# ESP32Breakout.net
KiCad netlist of a schematic drawn in EAGLE
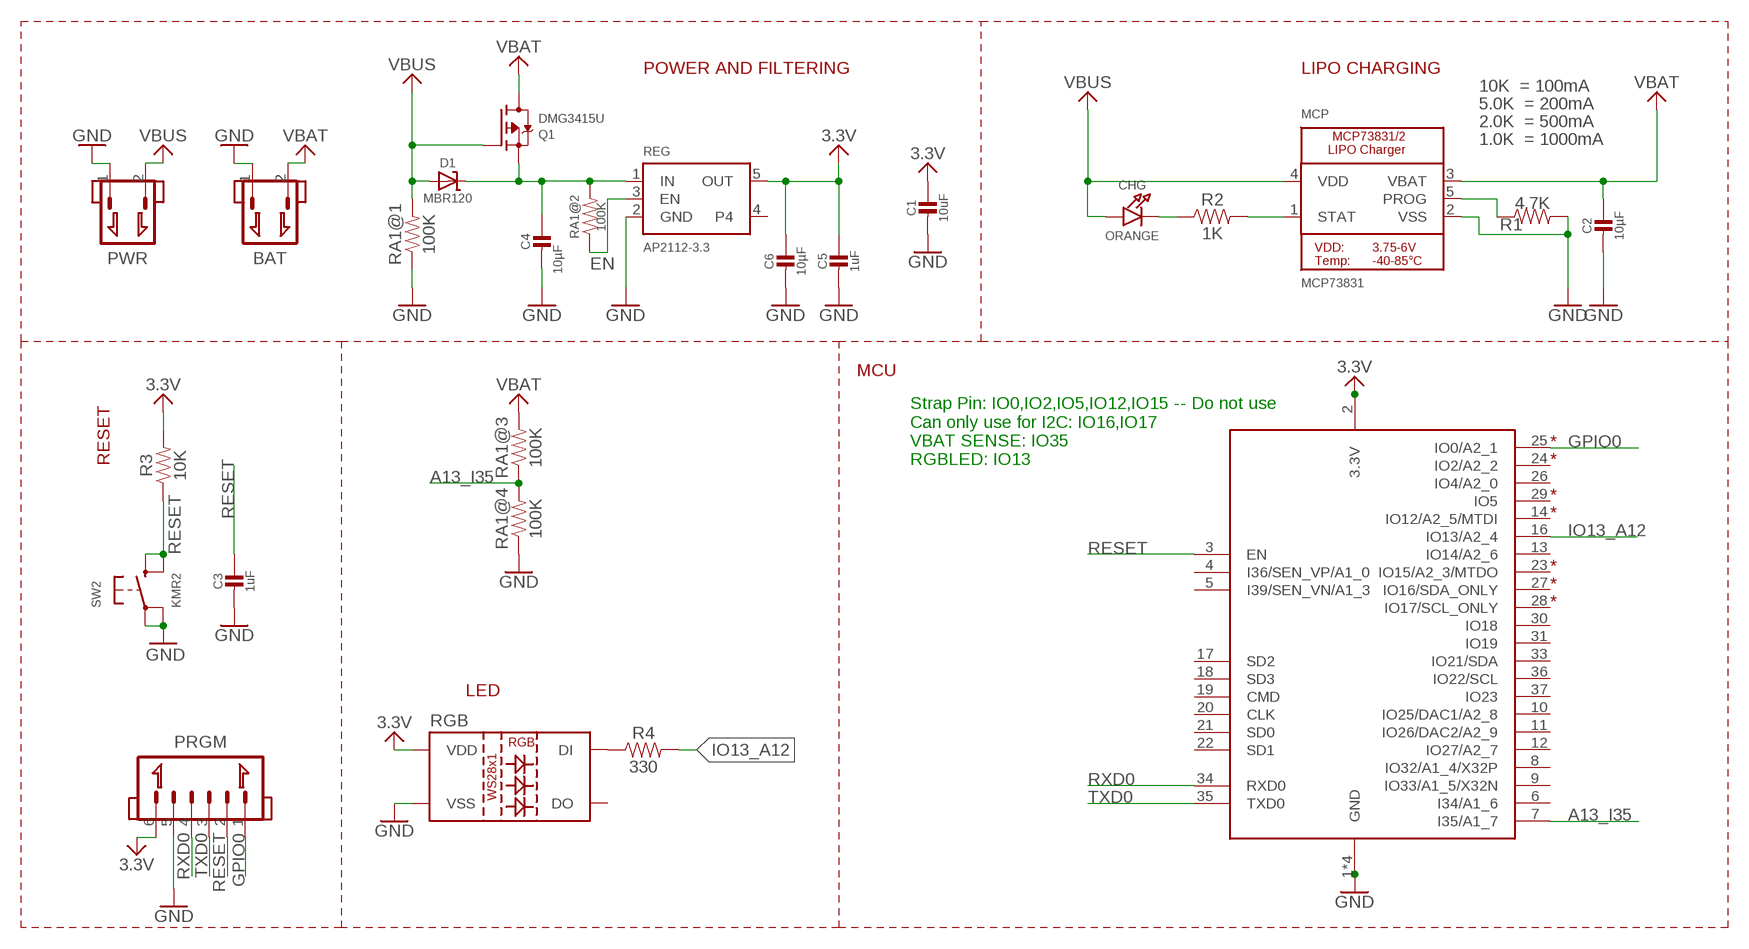
[diagram p0: schematic, sheet 1]

(export (version "E")
  (design (tool "Eeschema 10.0.6"))
  (components
    (comp (ref "BAT")
      (value "JSTPH")
      (footprint "eagle-import:JST_PH_2.0_2P")
      (libsource (lib "eagle-import") (part "JST_PH_2.0_2P"))
    )
    (comp (ref "C1")
      (value "10uF")
      (footprint "eagle-import:CAP_0805")
      (libsource (lib "eagle-import") (part "CAP_CERAMIC_0805"))
    )
    (comp (ref "C2")
      (value "10µF")
      (footprint "eagle-import:CAP_0805")
      (libsource (lib "eagle-import") (part "CAP_CERAMIC_0805"))
    )
    (comp (ref "C3")
      (value "1uF")
      (footprint "eagle-import:CAP_0603")
      (libsource (lib "eagle-import") (part "CAP_CERAMIC_0603"))
    )
    (comp (ref "C4")
      (value "10µF")
      (footprint "eagle-import:CAP_0603")
      (libsource (lib "eagle-import") (part "CAP_CERAMIC_0603"))
    )
    (comp (ref "C5")
      (value "1uF")
      (footprint "eagle-import:CAP_0603")
      (libsource (lib "eagle-import") (part "CAP_CERAMIC_0603"))
    )
    (comp (ref "C6")
      (value "10µF")
      (footprint "eagle-import:CAP_0805")
      (libsource (lib "eagle-import") (part "CAP_CERAMIC_0805"))
    )
    (comp (ref "CHG")
      (value "ORANGE")
      (footprint "eagle-import:MICROBUILDER_CHIPLED_0603")
      (libsource (lib "eagle-import") (part "LED0603"))
    )
    (comp (ref "D1")
      (value "MBR120")
      (footprint "eagle-import:SOD-123")
      (libsource (lib "eagle-import") (part "DIODE-SCHOTTKYSOD-123"))
    )
    (comp (ref "MCP")
      (value "MCP73831")
      (footprint "eagle-import:MICROBUILDER_SOT23-5")
      (libsource (lib "eagle-import") (part "MCP73831/2"))
    )
    (comp (ref "PRGM")
      (value "JST_1.25_6P")
      (footprint "eagle-import:JST1.25_6P")
      (libsource (lib "eagle-import") (part "JST_1.25_6P"))
    )
    (comp (ref "PWR")
      (value "JST_PH_2.0_2P")
      (footprint "eagle-import:JST_PH_2.0_2P")
      (libsource (lib "eagle-import") (part "JST_PH_2.0_2P"))
    )
    (comp (ref "Q1")
      (value "DMG3415U")
      (footprint "eagle-import:SOT23-WIDE")
      (libsource (lib "eagle-import") (part "MOSFET-PWIDE"))
    )
    (comp (ref "R1")
      (value "4.7K")
      (footprint "eagle-import:0603")
      (libsource (lib "eagle-import") (part "RESISTOR0603"))
    )
    (comp (ref "R2")
      (value "1K")
      (footprint "eagle-import:0603")
      (libsource (lib "eagle-import") (part "RESISTOR0603"))
    )
    (comp (ref "R3")
      (value "10K")
      (footprint "eagle-import:0603")
      (libsource (lib "eagle-import") (part "RESISTOR0603"))
    )
    (comp (ref "R4")
      (value "330")
      (footprint "eagle-import:0603")
      (libsource (lib "eagle-import") (part "RESISTOR0603"))
    )
    (comp (ref "RA1")
      (value "100K")
      (footprint "eagle-import:RESCAF80P320X160X60-8N")
      (libsource (lib "eagle-import") (part "RESISTOR_ARRAY_1206_SEPARATE"))
    )
    (comp (ref "REG")
      (value "AP2112-3.3")
      (footprint "eagle-import:MICROBUILDER_SOT23-5")
      (libsource (lib "eagle-import") (part "VREG_SOT23-5"))
    )
    (comp (ref "RGB")
      (value "LED_WS2812")
      (footprint "eagle-import:LED-TRICOLOR-5050-IC")
      (libsource (lib "eagle-import") (part "LED_WS2812"))
    )
    (comp (ref "SW2")
      (value "KMR2")
      (footprint "eagle-import:BTN_KMR2_4.6X2.8")
      (libsource (lib "eagle-import") (part "SWITCH_TACT_SMT4.6X2.8"))
    )
    (comp (ref "X2")
      (value "ESP32_WROOM32")
      (footprint "eagle-import:WROOM32")
      (libsource (lib "eagle-import") (part "ESP32_WROOM32"))
    )
  )
  (nets
    (net (code "1") (name "/A13_I35") (class "Default")
      (node (ref "RA1") (pin "3") (pinfunction "1_3") (pintype "passive"))
      (node (ref "RA1") (pin "8") (pinfunction "2_8") (pintype "passive"))
      (node (ref "X2") (pin "7") (pinfunction "I35/A1_7_7") (pintype "bidirectional"))
    )
    (net (code "2") (name "/EN") (class "Default")
      (node (ref "RA1") (pin "2") (pinfunction "1_2") (pintype "passive"))
      (node (ref "REG") (pin "3") (pinfunction "EN_3") (pintype "input"))
    )
    (net (code "3") (name "/GPIO0") (class "Default")
      (node (ref "PRGM") (pin "1") (pinfunction "1_1") (pintype "passive"))
      (node (ref "X2") (pin "25") (pinfunction "IO0/A2_1_25") (pintype "bidirectional"))
    )
    (net (code "4") (name "/RESET") (class "Default")
      (node (ref "C3") (pin "1") (pinfunction "1_1") (pintype "passive"))
      (node (ref "PRGM") (pin "2") (pinfunction "2_2") (pintype "passive"))
      (node (ref "R3") (pin "1") (pinfunction "1_1") (pintype "passive"))
      (node (ref "SW2") (pin "B") (pinfunction "S_B") (pintype "passive"))
      (node (ref "SW2") (pin "B'") (pinfunction "S1_B'") (pintype "passive"))
      (node (ref "X2") (pin "3") (pinfunction "EN_3") (pintype "input"))
    )
    (net (code "5") (name "/RXD0") (class "Default")
      (node (ref "PRGM") (pin "4") (pinfunction "4_4") (pintype "passive"))
      (node (ref "X2") (pin "34") (pinfunction "RXD0_34") (pintype "input"))
    )
    (net (code "6") (name "/TXD0") (class "Default")
      (node (ref "PRGM") (pin "3") (pinfunction "3_3") (pintype "passive"))
      (node (ref "X2") (pin "35") (pinfunction "TXD0_35") (pintype "output"))
    )
    (net (code "7") (name "GND") (class "Default")
      (node (ref "BAT") (pin "1") (pinfunction "1_1") (pintype "passive"))
      (node (ref "C1") (pin "2") (pinfunction "2_2") (pintype "passive"))
      (node (ref "C2") (pin "2") (pinfunction "2_2") (pintype "passive"))
      (node (ref "C3") (pin "2") (pinfunction "2_2") (pintype "passive"))
      (node (ref "C4") (pin "2") (pinfunction "2_2") (pintype "passive"))
      (node (ref "C5") (pin "2") (pinfunction "2_2") (pintype "passive"))
      (node (ref "C6") (pin "2") (pinfunction "2_2") (pintype "passive"))
      (node (ref "MCP") (pin "2") (pinfunction "VSS_2") (pintype "input"))
      (node (ref "PRGM") (pin "5") (pinfunction "5_5") (pintype "passive"))
      (node (ref "PWR") (pin "1") (pinfunction "1_1") (pintype "passive"))
      (node (ref "R1") (pin "2") (pinfunction "2_2") (pintype "passive"))
      (node (ref "RA1") (pin "1") (pinfunction "1_1") (pintype "passive"))
      (node (ref "RA1") (pin "4") (pinfunction "1_4") (pintype "passive"))
      (node (ref "REG") (pin "2") (pinfunction "GND_2") (pintype "input"))
      (node (ref "RGB") (pin "VSS") (pinfunction "VSS_VSS") (pintype "bidirectional"))
      (node (ref "SW2") (pin "A") (pinfunction "P_A") (pintype "passive"))
      (node (ref "SW2") (pin "A'") (pinfunction "P1_A'") (pintype "passive"))
      (node (ref "X2") (pin "1") (pinfunction "GND_1") (pintype "power_in"))
      (node (ref "X2") (pin "15") (pinfunction "GND_15") (pintype "power_in"))
      (node (ref "X2") (pin "38") (pinfunction "GND_38") (pintype "power_in"))
      (node (ref "X2") (pin "P$1") (pinfunction "GND_P$1") (pintype "power_in"))
    )
    (net (code "8") (name "IO13_A12") (class "Default")
      (node (ref "R4") (pin "2") (pinfunction "2_2") (pintype "passive"))
      (node (ref "X2") (pin "16") (pinfunction "IO13/A2_4_16") (pintype "bidirectional"))
    )
    (net (code "9") (name "Net-(CHG-PadC)") (class "Default")
      (node (ref "CHG") (pin "C") (pinfunction "C_C") (pintype "passive"))
      (node (ref "R2") (pin "1") (pinfunction "1_1") (pintype "passive"))
    )
    (net (code "10") (name "Net-(MCP-PROG)") (class "Default")
      (node (ref "MCP") (pin "5") (pinfunction "PROG_5") (pintype "input"))
      (node (ref "R1") (pin "1") (pinfunction "1_1") (pintype "passive"))
    )
    (net (code "11") (name "Net-(MCP-STAT)") (class "Default")
      (node (ref "MCP") (pin "1") (pinfunction "STAT_1") (pintype "output"))
      (node (ref "R2") (pin "2") (pinfunction "2_2") (pintype "passive"))
    )
    (net (code "12") (name "Net-(Q1-S)") (class "Default")
      (node (ref "C4") (pin "1") (pinfunction "1_1") (pintype "passive"))
      (node (ref "D1") (pin "C") (pinfunction "C_C") (pintype "passive"))
      (node (ref "Q1") (pin "2") (pinfunction "S_2") (pintype "passive"))
      (node (ref "RA1") (pin "6") (pinfunction "2_6") (pintype "passive"))
      (node (ref "REG") (pin "1") (pinfunction "IN_1") (pintype "input"))
    )
    (net (code "13") (name "Net-(RGB-DI)") (class "Default")
      (node (ref "R4") (pin "1") (pinfunction "1_1") (pintype "passive"))
      (node (ref "RGB") (pin "DIN") (pinfunction "DI_DIN") (pintype "bidirectional"))
    )
    (net (code "14") (name "SUPPLY_3.3V") (class "Default")
      (node (ref "C1") (pin "1") (pinfunction "1_1") (pintype "passive"))
      (node (ref "C5") (pin "1") (pinfunction "1_1") (pintype "passive"))
      (node (ref "C6") (pin "1") (pinfunction "1_1") (pintype "passive"))
      (node (ref "PRGM") (pin "6") (pinfunction "6_6") (pintype "passive"))
      (node (ref "R3") (pin "2") (pinfunction "2_2") (pintype "passive"))
      (node (ref "REG") (pin "5") (pinfunction "OUT_5") (pintype "passive"))
      (node (ref "RGB") (pin "VDD") (pinfunction "VDD_VDD") (pintype "bidirectional"))
      (node (ref "X2") (pin "2") (pinfunction "3.3V_2") (pintype "power_in"))
    )
    (net (code "15") (name "SUPPLY_VBAT") (class "Default")
      (node (ref "BAT") (pin "2") (pinfunction "2_2") (pintype "passive"))
      (node (ref "C2") (pin "1") (pinfunction "1_1") (pintype "passive"))
      (node (ref "MCP") (pin "3") (pinfunction "VBAT_3") (pintype "passive"))
      (node (ref "Q1") (pin "3") (pinfunction "D_3") (pintype "passive"))
      (node (ref "RA1") (pin "7") (pinfunction "2_7") (pintype "passive"))
    )
    (net (code "16") (name "SUPPLY_VBUS") (class "Default")
      (node (ref "CHG") (pin "A") (pinfunction "A_A") (pintype "passive"))
      (node (ref "D1") (pin "A") (pinfunction "A_A") (pintype "passive"))
      (node (ref "MCP") (pin "4") (pinfunction "VDD_4") (pintype "input"))
      (node (ref "PWR") (pin "2") (pinfunction "2_2") (pintype "passive"))
      (node (ref "Q1") (pin "1") (pinfunction "G_1") (pintype "passive"))
      (node (ref "RA1") (pin "5") (pinfunction "2_5") (pintype "passive"))
    )
    (net (code "17") (name "unconnected-(REG-P4-Pad4)") (class "Default")
      (node (ref "REG") (pin "4") (pinfunction "P4_4") (pintype "bidirectional"))
    )
    (net (code "18") (name "unconnected-(RGB-DO-PadDOUT)") (class "Default")
      (node (ref "RGB") (pin "DOUT") (pinfunction "DO_DOUT") (pintype "bidirectional"))
    )
    (net (code "19") (name "unconnected-(X2-CLK-Pad20)") (class "Default")
      (node (ref "X2") (pin "20") (pinfunction "CLK_20") (pintype "no_connect"))
    )
    (net (code "20") (name "unconnected-(X2-CMD-Pad19)") (class "Default")
      (node (ref "X2") (pin "19") (pinfunction "CMD_19") (pintype "no_connect"))
    )
    (net (code "21") (name "unconnected-(X2-I34{slash}A1_6-Pad6)") (class "Default")
      (node (ref "X2") (pin "6") (pinfunction "I34/A1_6_6") (pintype "bidirectional"))
    )
    (net (code "22") (name "unconnected-(X2-I36{slash}SEN_VP{slash}A1_0-Pad4)") (class "Default")
      (node (ref "X2") (pin "4") (pinfunction "I36/SEN_VP/A1_0_4") (pintype "bidirectional"))
    )
    (net (code "23") (name "unconnected-(X2-I39{slash}SEN_VN{slash}A1_3-Pad5)") (class "Default")
      (node (ref "X2") (pin "5") (pinfunction "I39/SEN_VN/A1_3_5") (pintype "bidirectional"))
    )
    (net (code "24") (name "unconnected-(X2-IO2{slash}A2_2-Pad24)") (class "Default")
      (node (ref "X2") (pin "24") (pinfunction "IO2/A2_2_24") (pintype "bidirectional"))
    )
    (net (code "25") (name "unconnected-(X2-IO4{slash}A2_0-Pad26)") (class "Default")
      (node (ref "X2") (pin "26") (pinfunction "IO4/A2_0_26") (pintype "bidirectional"))
    )
    (net (code "26") (name "unconnected-(X2-IO5-Pad29)") (class "Default")
      (node (ref "X2") (pin "29") (pinfunction "IO5_29") (pintype "bidirectional"))
    )
    (net (code "27") (name "unconnected-(X2-IO12{slash}A2_5{slash}MTDI-Pad14)") (class "Default")
      (node (ref "X2") (pin "14") (pinfunction "IO12/A2_5/MTDI_14") (pintype "bidirectional"))
    )
    (net (code "28") (name "unconnected-(X2-IO14{slash}A2_6-Pad13)") (class "Default")
      (node (ref "X2") (pin "13") (pinfunction "IO14/A2_6_13") (pintype "bidirectional"))
    )
    (net (code "29") (name "unconnected-(X2-IO15{slash}A2_3{slash}MTDO-Pad23)") (class "Default")
      (node (ref "X2") (pin "23") (pinfunction "IO15/A2_3/MTDO_23") (pintype "bidirectional"))
    )
    (net (code "30") (name "unconnected-(X2-IO16{slash}SDA_ONLY-Pad27)") (class "Default")
      (node (ref "X2") (pin "27") (pinfunction "IO16/SDA_ONLY_27") (pintype "bidirectional"))
    )
    (net (code "31") (name "unconnected-(X2-IO17{slash}SCL_ONLY-Pad28)") (class "Default")
      (node (ref "X2") (pin "28") (pinfunction "IO17/SCL_ONLY_28") (pintype "bidirectional"))
    )
    (net (code "32") (name "unconnected-(X2-IO18-Pad30)") (class "Default")
      (node (ref "X2") (pin "30") (pinfunction "IO18_30") (pintype "bidirectional"))
    )
    (net (code "33") (name "unconnected-(X2-IO19-Pad31)") (class "Default")
      (node (ref "X2") (pin "31") (pinfunction "IO19_31") (pintype "bidirectional"))
    )
    (net (code "34") (name "unconnected-(X2-IO21{slash}SDA-Pad33)") (class "Default")
      (node (ref "X2") (pin "33") (pinfunction "IO21/SDA_33") (pintype "bidirectional"))
    )
    (net (code "35") (name "unconnected-(X2-IO22{slash}SCL-Pad36)") (class "Default")
      (node (ref "X2") (pin "36") (pinfunction "IO22/SCL_36") (pintype "bidirectional"))
    )
    (net (code "36") (name "unconnected-(X2-IO23-Pad37)") (class "Default")
      (node (ref "X2") (pin "37") (pinfunction "IO23_37") (pintype "bidirectional"))
    )
    (net (code "37") (name "unconnected-(X2-IO25{slash}DAC1{slash}A2_8-Pad10)") (class "Default")
      (node (ref "X2") (pin "10") (pinfunction "IO25/DAC1/A2_8_10") (pintype "bidirectional"))
    )
    (net (code "38") (name "unconnected-(X2-IO26{slash}DAC2{slash}A2_9-Pad11)") (class "Default")
      (node (ref "X2") (pin "11") (pinfunction "IO26/DAC2/A2_9_11") (pintype "bidirectional"))
    )
    (net (code "39") (name "unconnected-(X2-IO27{slash}A2_7-Pad12)") (class "Default")
      (node (ref "X2") (pin "12") (pinfunction "IO27/A2_7_12") (pintype "bidirectional"))
    )
    (net (code "40") (name "unconnected-(X2-IO32{slash}A1_4{slash}X32P-Pad8)") (class "Default")
      (node (ref "X2") (pin "8") (pinfunction "IO32/A1_4/X32P_8") (pintype "bidirectional"))
    )
    (net (code "41") (name "unconnected-(X2-IO33{slash}A1_5{slash}X32N-Pad9)") (class "Default")
      (node (ref "X2") (pin "9") (pinfunction "IO33/A1_5/X32N_9") (pintype "bidirectional"))
    )
    (net (code "42") (name "unconnected-(X2-SD0-Pad21)") (class "Default")
      (node (ref "X2") (pin "21") (pinfunction "SD0_21") (pintype "no_connect"))
    )
    (net (code "43") (name "unconnected-(X2-SD1-Pad22)") (class "Default")
      (node (ref "X2") (pin "22") (pinfunction "SD1_22") (pintype "no_connect"))
    )
    (net (code "44") (name "unconnected-(X2-SD2-Pad17)") (class "Default")
      (node (ref "X2") (pin "17") (pinfunction "SD2_17") (pintype "no_connect"))
    )
    (net (code "45") (name "unconnected-(X2-SD3-Pad18)") (class "Default")
      (node (ref "X2") (pin "18") (pinfunction "SD3_18") (pintype "no_connect"))
    )
  )
)
